# table1.net
KiCad netlist of a schematic drawn in EasyEDA
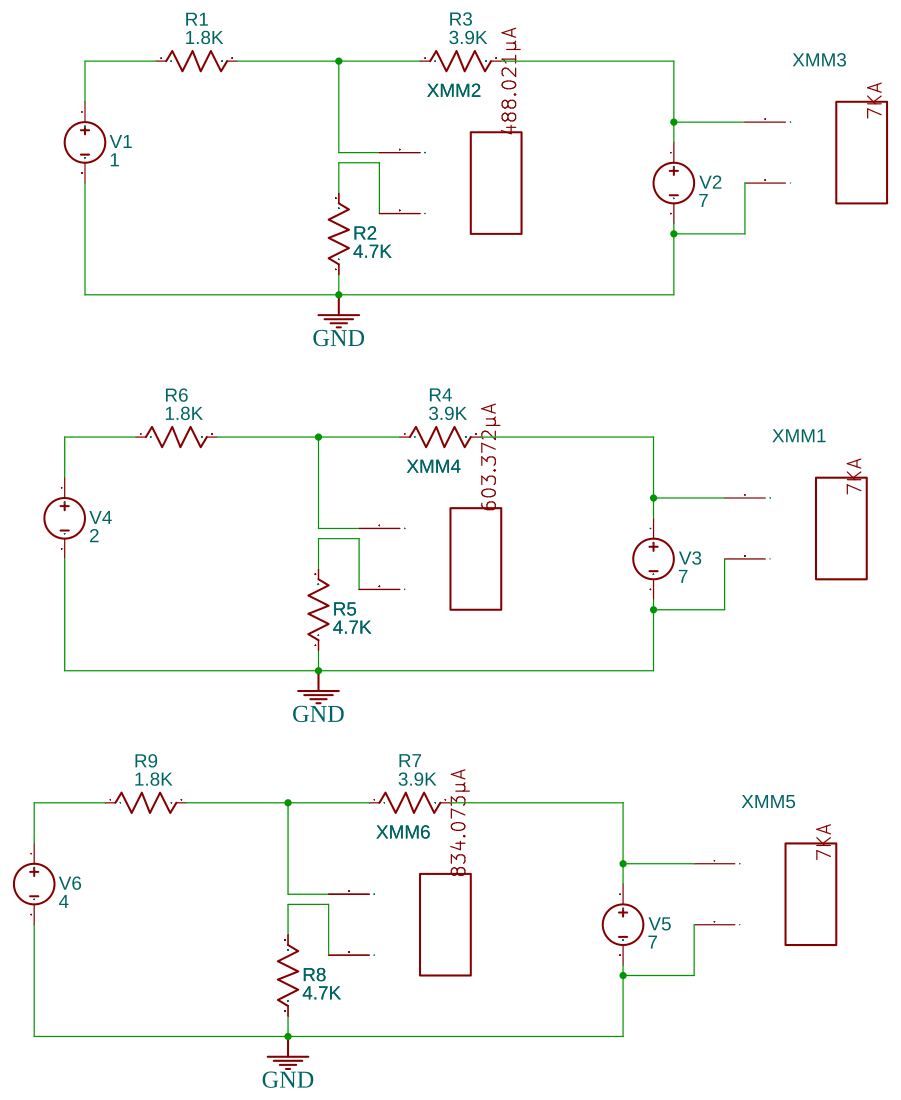
[diagram p0: schematic sheet]

(export (version "E")
  (design (tool "Eeschema 10.0.6"))
  (components
    (comp (ref "R1") (value "1.8K") (libsource (lib "") (part "Resistor_US_1")))
    (comp (ref "R2") (value "4.7K") (libsource (lib "") (part "Resistor_US")))
    (comp (ref "R3") (value "3.9K") (libsource (lib "") (part "Resistor_US_1")))
    (comp (ref "R4") (value "3.9K") (libsource (lib "") (part "Resistor_US_1")))
    (comp (ref "R5") (value "4.7K") (libsource (lib "") (part "Resistor_US")))
    (comp (ref "R6") (value "1.8K") (libsource (lib "") (part "Resistor_US_1")))
    (comp (ref "R7") (value "3.9K") (libsource (lib "") (part "Resistor_US_1")))
    (comp (ref "R8") (value "4.7K") (libsource (lib "") (part "Resistor_US")))
    (comp (ref "R9") (value "1.8K") (libsource (lib "") (part "Resistor_US_1")))
    (comp (ref "V1") (value "1") (libsource (lib "") (part "VDC")))
    (comp (ref "V2") (value "7") (libsource (lib "") (part "VDC")))
    (comp (ref "V3") (value "7") (libsource (lib "") (part "VDC")))
    (comp (ref "V4") (value "2") (libsource (lib "") (part "VDC")))
    (comp (ref "V5") (value "7") (libsource (lib "") (part "VDC")))
    (comp (ref "V6") (value "4") (libsource (lib "") (part "VDC")))
    (comp (ref "XMM1") (value "Multimeter") (libsource (lib "") (part "MULTIMETER")))
    (comp (ref "XMM2") (value "Multimeter") (libsource (lib "") (part "MULTIMETER_2")))
    (comp (ref "XMM3") (value "Multimeter") (libsource (lib "") (part "MULTIMETER")))
    (comp (ref "XMM4") (value "Multimeter") (libsource (lib "") (part "MULTIMETER_1")))
    (comp (ref "XMM5") (value "Multimeter") (libsource (lib "") (part "MULTIMETER")))
    (comp (ref "XMM6") (value "Multimeter") (libsource (lib "") (part "MULTIMETER_3")))
  )
  (nets
    (net (code "1") (name "GND") (class "Default")
      (node (ref "R2") (pin "1") (pinfunction "1_1") (pintype "unspecified"))
      (node (ref "R5") (pin "1") (pinfunction "1_1") (pintype "unspecified"))
      (node (ref "R8") (pin "1") (pinfunction "1_1") (pintype "unspecified"))
      (node (ref "V1") (pin "2") (pinfunction "2_2") (pintype "unspecified"))
      (node (ref "V2") (pin "2") (pinfunction "2_2") (pintype "unspecified"))
      (node (ref "V3") (pin "2") (pinfunction "2_2") (pintype "unspecified"))
      (node (ref "V4") (pin "2") (pinfunction "2_2") (pintype "unspecified"))
      (node (ref "V5") (pin "2") (pinfunction "2_2") (pintype "unspecified"))
      (node (ref "V6") (pin "2") (pinfunction "2_2") (pintype "unspecified"))
      (node (ref "XMM1") (pin "2") (pinfunction "I_2") (pintype "unspecified"))
      (node (ref "XMM3") (pin "2") (pinfunction "I_2") (pintype "unspecified"))
      (node (ref "XMM5") (pin "2") (pinfunction "I_2") (pintype "unspecified"))
    )
    (net (code "2") (name "Net-(R1-Pad1)") (class "Default")
      (node (ref "R1") (pin "1") (pinfunction "1_1") (pintype "unspecified"))
      (node (ref "V1") (pin "1") (pinfunction "1_1") (pintype "unspecified"))
    )
    (net (code "3") (name "Net-(R6-Pad1)") (class "Default")
      (node (ref "R6") (pin "1") (pinfunction "1_1") (pintype "unspecified"))
      (node (ref "V4") (pin "1") (pinfunction "1_1") (pintype "unspecified"))
    )
    (net (code "4") (name "Net-(R9-Pad1)") (class "Default")
      (node (ref "R9") (pin "1") (pinfunction "1_1") (pintype "unspecified"))
      (node (ref "V6") (pin "1") (pinfunction "1_1") (pintype "unspecified"))
    )
    (net (code "5") (name "Net-(XMM1-+)") (class "Default")
      (node (ref "R4") (pin "2") (pinfunction "2_2") (pintype "unspecified"))
      (node (ref "V3") (pin "1") (pinfunction "1_1") (pintype "unspecified"))
      (node (ref "XMM1") (pin "1") (pinfunction "+_1") (pintype "unspecified"))
    )
    (net (code "6") (name "Net-(XMM2-+)") (class "Default")
      (node (ref "R1") (pin "2") (pinfunction "2_2") (pintype "unspecified"))
      (node (ref "R3") (pin "1") (pinfunction "1_1") (pintype "unspecified"))
      (node (ref "XMM2") (pin "1") (pinfunction "+_1") (pintype "unspecified"))
    )
    (net (code "7") (name "Net-(XMM2-I)") (class "Default")
      (node (ref "R2") (pin "2") (pinfunction "2_2") (pintype "unspecified"))
      (node (ref "XMM2") (pin "2") (pinfunction "I_2") (pintype "unspecified"))
    )
    (net (code "8") (name "Net-(XMM3-+)") (class "Default")
      (node (ref "R3") (pin "2") (pinfunction "2_2") (pintype "unspecified"))
      (node (ref "V2") (pin "1") (pinfunction "1_1") (pintype "unspecified"))
      (node (ref "XMM3") (pin "1") (pinfunction "+_1") (pintype "unspecified"))
    )
    (net (code "9") (name "Net-(XMM4-+)") (class "Default")
      (node (ref "R4") (pin "1") (pinfunction "1_1") (pintype "unspecified"))
      (node (ref "R6") (pin "2") (pinfunction "2_2") (pintype "unspecified"))
      (node (ref "XMM4") (pin "1") (pinfunction "+_1") (pintype "unspecified"))
    )
    (net (code "10") (name "Net-(XMM4-I)") (class "Default")
      (node (ref "R5") (pin "2") (pinfunction "2_2") (pintype "unspecified"))
      (node (ref "XMM4") (pin "2") (pinfunction "I_2") (pintype "unspecified"))
    )
    (net (code "11") (name "Net-(XMM5-+)") (class "Default")
      (node (ref "R7") (pin "2") (pinfunction "2_2") (pintype "unspecified"))
      (node (ref "V5") (pin "1") (pinfunction "1_1") (pintype "unspecified"))
      (node (ref "XMM5") (pin "1") (pinfunction "+_1") (pintype "unspecified"))
    )
    (net (code "12") (name "Net-(XMM6-+)") (class "Default")
      (node (ref "R7") (pin "1") (pinfunction "1_1") (pintype "unspecified"))
      (node (ref "R9") (pin "2") (pinfunction "2_2") (pintype "unspecified"))
      (node (ref "XMM6") (pin "1") (pinfunction "+_1") (pintype "unspecified"))
    )
    (net (code "13") (name "Net-(XMM6-I)") (class "Default")
      (node (ref "R8") (pin "2") (pinfunction "2_2") (pintype "unspecified"))
      (node (ref "XMM6") (pin "2") (pinfunction "I_2") (pintype "unspecified"))
    )
  )
)
